# JLINK_OB_072.net
KiCad netlist of a schematic drawn in Altium Designer
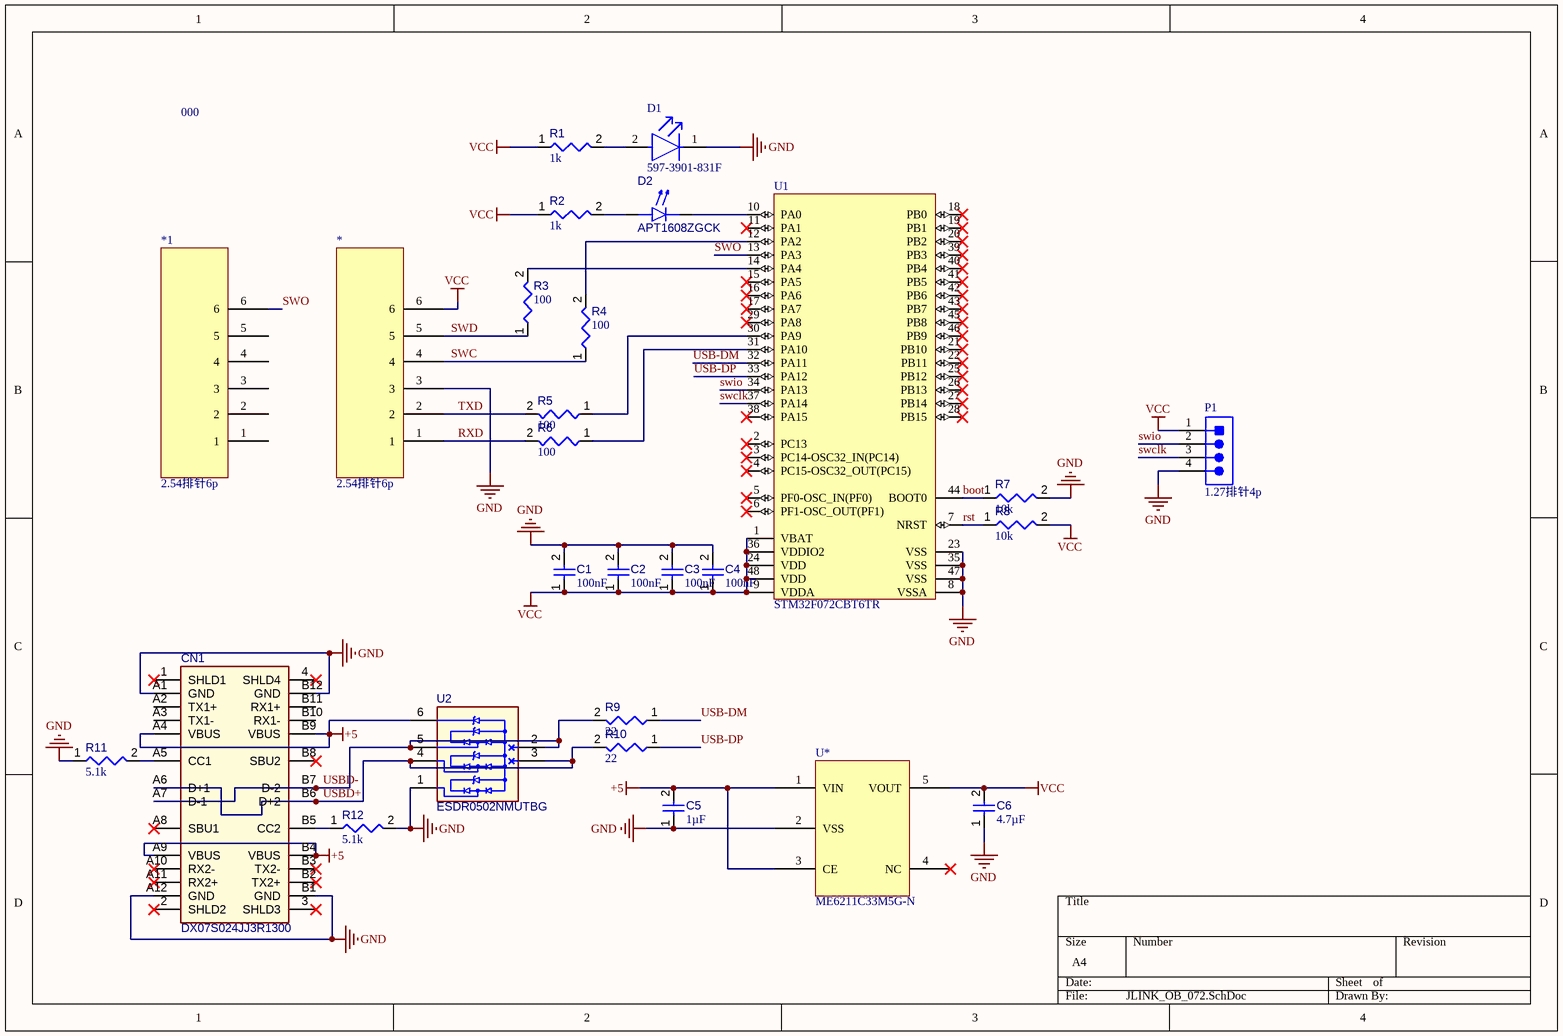
[diagram p0: JLINK_OB_072.SchDoc]

(export (version "E")
  (design (tool "Eeschema 10.0.6"))
  (components
    (comp (ref "*")
      (value "2.54排针6p")
      (footprint "HDR2.54-WS-6P")
      (libsource (lib "DigiPCBA Workspace") (part "2.54排针6p-Symbol-1"))
    )
    (comp (ref "*1")
      (value "2.54排针6p")
      (footprint "HDR2.54-WS-6P")
      (libsource (lib "DigiPCBA Workspace") (part "2.54排针6p-Symbol-1"))
    )
    (comp (ref "C1")
      (value "100nF")
      (footprint "CAPC1608X90X40NL10T20")
      (description "Chip Capacitor, 100 nF, +/- 10%, 50 V, 0603 (1608 Metric)")
      (fields (field (name "TOLERANCE") "10%") (field (name "Comment") "Capacitor 100 nF +/-10% 50 V 0603"))
      (libsource (lib "DigiPCBA Workspace") (part "CAP-NP-2"))
    )
    (comp (ref "C2")
      (value "100nF")
      (footprint "CAPC1608X90X40NL10T20")
      (description "Chip Capacitor, 100 nF, +/- 10%, 50 V, 0603 (1608 Metric)")
      (fields (field (name "TOLERANCE") "10%") (field (name "Comment") "Capacitor 100 nF +/-10% 50 V 0603"))
      (libsource (lib "DigiPCBA Workspace") (part "CAP-NP-2"))
    )
    (comp (ref "C3")
      (value "100nF")
      (footprint "CAPC1608X90X40NL10T20")
      (description "Chip Capacitor, 100 nF, +/- 10%, 50 V, 0603 (1608 Metric)")
      (fields (field (name "TOLERANCE") "10%") (field (name "Comment") "Capacitor 100 nF +/-10% 50 V 0603"))
      (libsource (lib "DigiPCBA Workspace") (part "CAP-NP-2"))
    )
    (comp (ref "C4")
      (value "100nF")
      (footprint "CAPC1608X90X40NL10T20")
      (description "Chip Capacitor, 100 nF, +/- 10%, 50 V, 0603 (1608 Metric)")
      (fields (field (name "TOLERANCE") "10%") (field (name "Comment") "Capacitor 100 nF +/-10% 50 V 0603"))
      (libsource (lib "DigiPCBA Workspace") (part "CAP-NP-2"))
    )
    (comp (ref "C5")
      (value "1µF")
      (footprint "CAPC1608X90X40LL10T20")
      (description "Chip Capacitor, 1 uF, +/- 10%, 25 V, 0603 (1608 Metric)")
      (fields (field (name "TOLERANCE") "10%") (field (name "Comment") "Capacitor 1 uF +/- 10% 25 V 0603"))
      (libsource (lib "DigiPCBA Workspace") (part "CAP-NP-2"))
    )
    (comp (ref "C6")
      (value "4.7µF")
      (footprint "CAPC0603(1608)100_L")
      (description "Chip Capacitor, 4.7µF +/-20%, 10V, 0603, Thickness 1 mm")
      (fields (field (name "TOLERANCE") "10%") (field (name "Comment") "Capacitor 4.7µF +/-20% 10V 0603"))
      (libsource (lib "DigiPCBA Workspace") (part "CAP-NP-2"))
    )
    (comp (ref "CN1")
      (value "DX07S024JJ3R1300")
      (footprint "JAE-DX07S024JJ3_V")
      (description "USB-C Connector, 20 V, 1.25 A, -30 to 80 degC, RoHS, Tape and Reel")
      (libsource (lib "DigiPCBA Workspace") (part "CMP-00171-5"))
    )
    (comp (ref "D1")
      (value "597-3901-831F")
      (footprint "FP-597-3901-831F-MFG")
      (description "Smd 0603 White 20Pc Smpl Strip / Dialight Corporation Rohs Compliant: Yes")
      (libsource (lib "DigiPCBA Workspace") (part "8706943c75ba83719d021d2fdc84c58"))
    )
    (comp (ref "D2")
      (value "APT1608ZGCK")
      (footprint "FP-APT1608ZGCK-MFG")
      (description "LED Uni-Color Green 515nm 2-Pin Chip LED T/R")
      (libsource (lib "DigiPCBA Workspace") (part "DIODE-LED-2"))
    )
    (comp (ref "P1")
      (value "1.27排针4p")
      (footprint "HDR1.27-LI-4P")
      (libsource (lib "DigiPCBA Workspace") (part "4p*1"))
    )
    (comp (ref "R1")
      (value "1k")
      (footprint "RESC1608X55X25ML10T15")
      (description "Chip Resistor, 1 KOhm, +/-1%, 0.1 W, -55 to 155 degC, 0603 (1608 Metric)")
      (fields (field (name "POWER") "100mW") (field (name "TOLERANCE") "1%"))
      (libsource (lib "DigiPCBA Workspace") (part "RES-2"))
    )
    (comp (ref "R2")
      (value "1k")
      (footprint "RESC1608X55X25ML10T15")
      (description "Chip Resistor, 1 KOhm, +/-1%, 0.1 W, -55 to 155 degC, 0603 (1608 Metric)")
      (fields (field (name "POWER") "100mW") (field (name "TOLERANCE") "1%"))
      (libsource (lib "DigiPCBA Workspace") (part "RES-2"))
    )
    (comp (ref "R3")
      (value "100")
      (footprint "FP-RC0603-0_55-MFG")
      (description "Res Thick Film 0603 100 Ohm 5% 1/10W ±100ppm/°C Molded SMD SMD Paper T/R")
      (fields (field (name "TOLERANCE") "5%") (field (name "Comment") "RC0603JR-07100RL"))
      (libsource (lib "DigiPCBA Workspace") (part "RES-2"))
    )
    (comp (ref "R4")
      (value "100")
      (footprint "FP-RC0603-0_55-MFG")
      (description "Res Thick Film 0603 100 Ohm 5% 1/10W ±100ppm/°C Molded SMD SMD Paper T/R")
      (fields (field (name "TOLERANCE") "5%") (field (name "Comment") "RC0603JR-07100RL"))
      (libsource (lib "DigiPCBA Workspace") (part "RES-2"))
    )
    (comp (ref "R5")
      (value "100")
      (footprint "FP-RC0603-0_55-MFG")
      (description "Res Thick Film 0603 100 Ohm 5% 1/10W ±100ppm/°C Molded SMD SMD Paper T/R")
      (fields (field (name "TOLERANCE") "5%") (field (name "Comment") "RC0603JR-07100RL"))
      (libsource (lib "DigiPCBA Workspace") (part "RES-2"))
    )
    (comp (ref "R6")
      (value "100")
      (footprint "FP-RC0603-0_55-MFG")
      (description "Res Thick Film 0603 100 Ohm 5% 1/10W ±100ppm/°C Molded SMD SMD Paper T/R")
      (fields (field (name "TOLERANCE") "5%") (field (name "Comment") "RC0603JR-07100RL"))
      (libsource (lib "DigiPCBA Workspace") (part "RES-2"))
    )
    (comp (ref "R7")
      (value "10k")
      (footprint "RESC1608X55X25ML10T15")
      (description "Chip Resistor, 10 KOhm, +/- 1%, 01 W, -55 to 155 degC, 0603 (1608 Metric)")
      (fields (field (name "POWER") "100mW") (field (name "TOLERANCE") "1%"))
      (libsource (lib "DigiPCBA Workspace") (part "RES-2"))
    )
    (comp (ref "R8")
      (value "10k")
      (footprint "RESC1608X55X25ML10T15")
      (description "Chip Resistor, 10 KOhm, +/- 1%, 01 W, -55 to 155 degC, 0603 (1608 Metric)")
      (fields (field (name "POWER") "100mW") (field (name "TOLERANCE") "1%"))
      (libsource (lib "DigiPCBA Workspace") (part "RES-2"))
    )
    (comp (ref "R9")
      (value "22")
      (footprint "RESC1609X50X30ML08T20")
      (description "Chip Resistor, 22 Ohm, +/- 1%, 100 mW, -55 to 155 degC, 0603 (1608 Metric)")
      (fields (field (name "POWER") "100mW") (field (name "TOLERANCE") "1%"))
      (libsource (lib "DigiPCBA Workspace") (part "RES-2"))
    )
    (comp (ref "R10")
      (value "22")
      (footprint "RESC1609X50X30ML08T20")
      (description "Chip Resistor, 22 Ohm, +/- 1%, 100 mW, -55 to 155 degC, 0603 (1608 Metric)")
      (fields (field (name "POWER") "100mW") (field (name "TOLERANCE") "1%"))
      (libsource (lib "DigiPCBA Workspace") (part "RES-2"))
    )
    (comp (ref "R11")
      (value "5.1k")
      (footprint "FP-RC1608-MFG")
      (description "Res Thick Film 0603 5.1K Ohm 5% 1/10W ±100ppm/°C Molded SMD SMD T/R")
      (fields (field (name "TOLERANCE") "5%") (field (name "Comment") "RC1608J512CS"))
      (libsource (lib "DigiPCBA Workspace") (part "RES-2"))
    )
    (comp (ref "R12")
      (value "5.1k")
      (footprint "FP-RC1608-MFG")
      (description "Res Thick Film 0603 5.1K Ohm 5% 1/10W ±100ppm/°C Molded SMD SMD T/R")
      (fields (field (name "TOLERANCE") "5%") (field (name "Comment") "RC1608J512CS"))
      (libsource (lib "DigiPCBA Workspace") (part "RES-2"))
    )
    (comp (ref "U*")
      (value "ME6211C33M5G-N")
      (footprint "SOT23-5N")
      (description "VIN=6.5V Vo=3.3V Io=600mA")
      (libsource (lib "DigiPCBA Workspace") (part "ME6211C33M5G-N-Symbol-1"))
    )
    (comp (ref "U1")
      (value "STM32F072CBT6TR")
      (footprint "LQFP48 7X7_N")
      (description "MCU 32-Bit GP STM32F 32MHz ARM Cortex M0+ RISC 128kB Flash 48-Pin LQFP T/R")
      (libsource (lib "DigiPCBA Workspace") (part "MC-ARM-STM32F07X-LQFP48"))
    )
    (comp (ref "U2")
      (value "ESDR0502NMUTBG")
      (footprint "ONSC-UDFN-6-517AA-01_V")
      (libsource (lib "DigiPCBA Workspace") (part "CMP-00124-4"))
    )
  )
  (nets
    (net (code "1") (name "+5") (class "Default")
      (node (ref "C5") (pin "2") (pinfunction "2_2") (pintype "passive"))
      (node (ref "CN1") (pin "A4") (pinfunction "VBUS_A4") (pintype "passive"))
      (node (ref "CN1") (pin "A9") (pinfunction "VBUS_A9") (pintype "passive"))
      (node (ref "CN1") (pin "B4") (pinfunction "VBUS_B4") (pintype "passive"))
      (node (ref "CN1") (pin "B9") (pinfunction "VBUS_B9") (pintype "passive"))
      (node (ref "U*") (pin "1") (pinfunction "VIN_1") (pintype "passive"))
      (node (ref "U*") (pin "3") (pinfunction "CE_3") (pintype "passive"))
      (node (ref "U2") (pin "6") (pinfunction "VBUS_6") (pintype "power_in"))
    )
    (net (code "2") (name "/RXD") (class "Default")
      (node (ref "*") (pin "1") (pinfunction "1_1") (pintype "passive"))
      (node (ref "R6") (pin "2") (pinfunction "2_2") (pintype "passive"))
    )
    (net (code "3") (name "/SWC") (class "Default")
      (node (ref "*") (pin "4") (pinfunction "4_4") (pintype "passive"))
      (node (ref "R4") (pin "1") (pinfunction "1_1") (pintype "passive"))
    )
    (net (code "4") (name "/SWD") (class "Default")
      (node (ref "*") (pin "5") (pinfunction "5_5") (pintype "passive"))
      (node (ref "R3") (pin "1") (pinfunction "1_1") (pintype "passive"))
    )
    (net (code "5") (name "/SWO") (class "Default")
      (node (ref "*1") (pin "6") (pinfunction "6_6") (pintype "passive"))
      (node (ref "U1") (pin "13") (pinfunction "PA3_13") (pintype "bidirectional"))
    )
    (net (code "6") (name "/TXD") (class "Default")
      (node (ref "*") (pin "2") (pinfunction "2_2") (pintype "passive"))
      (node (ref "R5") (pin "2") (pinfunction "2_2") (pintype "passive"))
    )
    (net (code "7") (name "/USB-DM") (class "Default")
      (node (ref "R9") (pin "1") (pinfunction "1_1") (pintype "passive"))
      (node (ref "U1") (pin "32") (pinfunction "PA11_32") (pintype "bidirectional"))
    )
    (net (code "8") (name "/USB-DP") (class "Default")
      (node (ref "R10") (pin "1") (pinfunction "1_1") (pintype "passive"))
      (node (ref "U1") (pin "33") (pinfunction "PA12_33") (pintype "bidirectional"))
    )
    (net (code "9") (name "/USBD+") (class "Default")
      (node (ref "CN1") (pin "A6") (pinfunction "D+1_A6") (pintype "passive"))
      (node (ref "CN1") (pin "B6") (pinfunction "D+2_B6") (pintype "passive"))
      (node (ref "R10") (pin "2") (pinfunction "2_2") (pintype "passive"))
      (node (ref "U2") (pin "3") (pinfunction "NC_3") (pintype "passive"))
      (node (ref "U2") (pin "4") (pinfunction "D-_4") (pintype "passive"))
    )
    (net (code "10") (name "/USBD-") (class "Default")
      (node (ref "CN1") (pin "A7") (pinfunction "D-1_A7") (pintype "passive"))
      (node (ref "CN1") (pin "B7") (pinfunction "D-2_B7") (pintype "passive"))
      (node (ref "R9") (pin "2") (pinfunction "2_2") (pintype "passive"))
      (node (ref "U2") (pin "2") (pinfunction "NC_2") (pintype "passive"))
      (node (ref "U2") (pin "5") (pinfunction "D+_5") (pintype "passive"))
    )
    (net (code "11") (name "/boot") (class "Default")
      (node (ref "R7") (pin "1") (pinfunction "1_1") (pintype "passive"))
      (node (ref "U1") (pin "44") (pinfunction "BOOT0_44") (pintype "passive"))
    )
    (net (code "12") (name "/rst") (class "Default")
      (node (ref "R8") (pin "1") (pinfunction "1_1") (pintype "passive"))
      (node (ref "U1") (pin "7") (pinfunction "NRST_7") (pintype "bidirectional"))
    )
    (net (code "13") (name "/swclk") (class "Default")
      (node (ref "P1") (pin "3") (pinfunction "3_3") (pintype "passive"))
      (node (ref "U1") (pin "37") (pinfunction "PA14_37") (pintype "bidirectional"))
    )
    (net (code "14") (name "/swio") (class "Default")
      (node (ref "P1") (pin "2") (pinfunction "2_2") (pintype "passive"))
      (node (ref "U1") (pin "34") (pinfunction "PA13_34") (pintype "bidirectional"))
    )
    (net (code "15") (name "GND") (class "Default")
      (node (ref "*") (pin "3") (pinfunction "3_3") (pintype "passive"))
      (node (ref "C1") (pin "2") (pinfunction "2_2") (pintype "passive"))
      (node (ref "C2") (pin "2") (pinfunction "2_2") (pintype "passive"))
      (node (ref "C3") (pin "2") (pinfunction "2_2") (pintype "passive"))
      (node (ref "C4") (pin "2") (pinfunction "2_2") (pintype "passive"))
      (node (ref "C5") (pin "1") (pinfunction "1_1") (pintype "passive"))
      (node (ref "C6") (pin "1") (pinfunction "1_1") (pintype "passive"))
      (node (ref "CN1") (pin "A1") (pinfunction "GND_A1") (pintype "passive"))
      (node (ref "CN1") (pin "A12") (pinfunction "GND_A12") (pintype "passive"))
      (node (ref "CN1") (pin "B1") (pinfunction "GND_B1") (pintype "passive"))
      (node (ref "CN1") (pin "B12") (pinfunction "GND_B12") (pintype "passive"))
      (node (ref "D1") (pin "1") (pinfunction "C_1") (pintype "passive"))
      (node (ref "P1") (pin "4") (pinfunction "4_4") (pintype "passive"))
      (node (ref "R11") (pin "1") (pinfunction "1_1") (pintype "passive"))
      (node (ref "R12") (pin "2") (pinfunction "2_2") (pintype "passive"))
      (node (ref "R7") (pin "2") (pinfunction "2_2") (pintype "passive"))
      (node (ref "U*") (pin "2") (pinfunction "VSS_2") (pintype "passive"))
      (node (ref "U1") (pin "23") (pinfunction "VSS_23") (pintype "power_in"))
      (node (ref "U1") (pin "35") (pinfunction "VSS_35") (pintype "power_in"))
      (node (ref "U1") (pin "47") (pinfunction "VSS_47") (pintype "power_in"))
      (node (ref "U1") (pin "8") (pinfunction "VSSA_8") (pintype "power_in"))
      (node (ref "U2") (pin "1") (pinfunction "GND_1") (pintype "power_in"))
    )
    (net (code "16") (name "Net-(CN1-CC1)") (class "Default")
      (node (ref "CN1") (pin "A5") (pinfunction "CC1_A5") (pintype "passive"))
      (node (ref "R11") (pin "2") (pinfunction "2_2") (pintype "passive"))
    )
    (net (code "17") (name "Net-(CN1-CC2)") (class "Default")
      (node (ref "CN1") (pin "B5") (pinfunction "CC2_B5") (pintype "passive"))
      (node (ref "R12") (pin "1") (pinfunction "1_1") (pintype "passive"))
    )
    (net (code "18") (name "Net-(D1-A)") (class "Default")
      (node (ref "D1") (pin "2") (pinfunction "A_2") (pintype "passive"))
      (node (ref "R1") (pin "2") (pinfunction "2_2") (pintype "passive"))
    )
    (net (code "19") (name "Net-(D2-A)") (class "Default")
      (node (ref "D2") (pin "2") (pinfunction "A_2") (pintype "passive"))
      (node (ref "R2") (pin "2") (pinfunction "2_2") (pintype "passive"))
    )
    (net (code "20") (name "Net-(D2-K)") (class "Default")
      (node (ref "D2") (pin "1") (pinfunction "K_1") (pintype "passive"))
      (node (ref "U1") (pin "10") (pinfunction "PA0_10") (pintype "bidirectional"))
    )
    (net (code "21") (name "Net-(U1-PA2)") (class "Default")
      (node (ref "R4") (pin "2") (pinfunction "2_2") (pintype "passive"))
      (node (ref "U1") (pin "12") (pinfunction "PA2_12") (pintype "bidirectional"))
    )
    (net (code "22") (name "Net-(U1-PA4)") (class "Default")
      (node (ref "R3") (pin "2") (pinfunction "2_2") (pintype "passive"))
      (node (ref "U1") (pin "14") (pinfunction "PA4_14") (pintype "bidirectional"))
    )
    (net (code "23") (name "Net-(U1-PA9)") (class "Default")
      (node (ref "R5") (pin "1") (pinfunction "1_1") (pintype "passive"))
      (node (ref "U1") (pin "30") (pinfunction "PA9_30") (pintype "bidirectional"))
    )
    (net (code "24") (name "Net-(U1-PA10)") (class "Default")
      (node (ref "R6") (pin "1") (pinfunction "1_1") (pintype "passive"))
      (node (ref "U1") (pin "31") (pinfunction "PA10_31") (pintype "bidirectional"))
    )
    (net (code "25") (name "VCC") (class "Default")
      (node (ref "*") (pin "6") (pinfunction "6_6") (pintype "passive"))
      (node (ref "C1") (pin "1") (pinfunction "1_1") (pintype "passive"))
      (node (ref "C2") (pin "1") (pinfunction "1_1") (pintype "passive"))
      (node (ref "C3") (pin "1") (pinfunction "1_1") (pintype "passive"))
      (node (ref "C4") (pin "1") (pinfunction "1_1") (pintype "passive"))
      (node (ref "C6") (pin "2") (pinfunction "2_2") (pintype "passive"))
      (node (ref "P1") (pin "1") (pinfunction "1_1") (pintype "passive"))
      (node (ref "R1") (pin "1") (pinfunction "1_1") (pintype "passive"))
      (node (ref "R2") (pin "1") (pinfunction "1_1") (pintype "passive"))
      (node (ref "R8") (pin "2") (pinfunction "2_2") (pintype "passive"))
      (node (ref "U*") (pin "5") (pinfunction "VOUT_5") (pintype "passive"))
      (node (ref "U1") (pin "1") (pinfunction "VBAT_1") (pintype "power_in"))
      (node (ref "U1") (pin "24") (pinfunction "VDD_24") (pintype "power_in"))
      (node (ref "U1") (pin "36") (pinfunction "VDDIO2_36") (pintype "power_in"))
      (node (ref "U1") (pin "48") (pinfunction "VDD_48") (pintype "power_in"))
      (node (ref "U1") (pin "9") (pinfunction "VDDA_9") (pintype "power_in"))
    )
    (net (code "26") (name "unconnected-(*1-Pad1)") (class "Default")
      (node (ref "*1") (pin "1") (pinfunction "1_1") (pintype "passive"))
    )
    (net (code "27") (name "unconnected-(*1-Pad2)") (class "Default")
      (node (ref "*1") (pin "2") (pinfunction "2_2") (pintype "passive"))
    )
    (net (code "28") (name "unconnected-(*1-Pad3)") (class "Default")
      (node (ref "*1") (pin "3") (pinfunction "3_3") (pintype "passive"))
    )
    (net (code "29") (name "unconnected-(*1-Pad4)") (class "Default")
      (node (ref "*1") (pin "4") (pinfunction "4_4") (pintype "passive"))
    )
    (net (code "30") (name "unconnected-(*1-Pad5)") (class "Default")
      (node (ref "*1") (pin "5") (pinfunction "5_5") (pintype "passive"))
    )
    (net (code "31") (name "unconnected-(CN1-RX1+-PadB11)") (class "Default")
      (node (ref "CN1") (pin "B11") (pinfunction "RX1+_B11") (pintype "passive"))
    )
    (net (code "32") (name "unconnected-(CN1-RX1--PadB10)") (class "Default")
      (node (ref "CN1") (pin "B10") (pinfunction "RX1-_B10") (pintype "passive"))
    )
    (net (code "33") (name "unconnected-(CN1-RX2+-PadA11)") (class "Default")
      (node (ref "CN1") (pin "A11") (pinfunction "RX2+_A11") (pintype "passive+no_connect"))
    )
    (net (code "34") (name "unconnected-(CN1-RX2--PadA10)") (class "Default")
      (node (ref "CN1") (pin "A10") (pinfunction "RX2-_A10") (pintype "passive+no_connect"))
    )
    (net (code "35") (name "unconnected-(CN1-SBU1-PadA8)") (class "Default")
      (node (ref "CN1") (pin "A8") (pinfunction "SBU1_A8") (pintype "passive+no_connect"))
    )
    (net (code "36") (name "unconnected-(CN1-SBU2-PadB8)") (class "Default")
      (node (ref "CN1") (pin "B8") (pinfunction "SBU2_B8") (pintype "passive+no_connect"))
    )
    (net (code "37") (name "unconnected-(CN1-SHLD1-Pad1)") (class "Default")
      (node (ref "CN1") (pin "1") (pinfunction "SHLD1_1") (pintype "passive+no_connect"))
    )
    (net (code "38") (name "unconnected-(CN1-SHLD2-Pad2)") (class "Default")
      (node (ref "CN1") (pin "2") (pinfunction "SHLD2_2") (pintype "passive+no_connect"))
    )
    (net (code "39") (name "unconnected-(CN1-SHLD3-Pad3)") (class "Default")
      (node (ref "CN1") (pin "3") (pinfunction "SHLD3_3") (pintype "passive+no_connect"))
    )
    (net (code "40") (name "unconnected-(CN1-SHLD4-Pad4)") (class "Default")
      (node (ref "CN1") (pin "4") (pinfunction "SHLD4_4") (pintype "passive+no_connect"))
    )
    (net (code "41") (name "unconnected-(CN1-TX1+-PadA2)") (class "Default")
      (node (ref "CN1") (pin "A2") (pinfunction "TX1+_A2") (pintype "passive"))
    )
    (net (code "42") (name "unconnected-(CN1-TX1--PadA3)") (class "Default")
      (node (ref "CN1") (pin "A3") (pinfunction "TX1-_A3") (pintype "passive"))
    )
    (net (code "43") (name "unconnected-(CN1-TX2+-PadB2)") (class "Default")
      (node (ref "CN1") (pin "B2") (pinfunction "TX2+_B2") (pintype "passive+no_connect"))
    )
    (net (code "44") (name "unconnected-(CN1-TX2--PadB3)") (class "Default")
      (node (ref "CN1") (pin "B3") (pinfunction "TX2-_B3") (pintype "passive+no_connect"))
    )
    (net (code "45") (name "unconnected-(U*-NC-Pad4)") (class "Default")
      (node (ref "U*") (pin "4") (pinfunction "NC_4") (pintype "passive+no_connect"))
    )
    (net (code "46") (name "unconnected-(U1-PA1-Pad11)") (class "Default")
      (node (ref "U1") (pin "11") (pinfunction "PA1_11") (pintype "bidirectional+no_connect"))
    )
    (net (code "47") (name "unconnected-(U1-PA5-Pad15)") (class "Default")
      (node (ref "U1") (pin "15") (pinfunction "PA5_15") (pintype "bidirectional+no_connect"))
    )
    (net (code "48") (name "unconnected-(U1-PA6-Pad16)") (class "Default")
      (node (ref "U1") (pin "16") (pinfunction "PA6_16") (pintype "bidirectional+no_connect"))
    )
    (net (code "49") (name "unconnected-(U1-PA7-Pad17)") (class "Default")
      (node (ref "U1") (pin "17") (pinfunction "PA7_17") (pintype "bidirectional+no_connect"))
    )
    (net (code "50") (name "unconnected-(U1-PA8-Pad29)") (class "Default")
      (node (ref "U1") (pin "29") (pinfunction "PA8_29") (pintype "bidirectional+no_connect"))
    )
    (net (code "51") (name "unconnected-(U1-PA15-Pad38)") (class "Default")
      (node (ref "U1") (pin "38") (pinfunction "PA15_38") (pintype "bidirectional+no_connect"))
    )
    (net (code "52") (name "unconnected-(U1-PB0-Pad18)") (class "Default")
      (node (ref "U1") (pin "18") (pinfunction "PB0_18") (pintype "bidirectional+no_connect"))
    )
    (net (code "53") (name "unconnected-(U1-PB1-Pad19)") (class "Default")
      (node (ref "U1") (pin "19") (pinfunction "PB1_19") (pintype "bidirectional+no_connect"))
    )
    (net (code "54") (name "unconnected-(U1-PB2-Pad20)") (class "Default")
      (node (ref "U1") (pin "20") (pinfunction "PB2_20") (pintype "bidirectional+no_connect"))
    )
    (net (code "55") (name "unconnected-(U1-PB3-Pad39)") (class "Default")
      (node (ref "U1") (pin "39") (pinfunction "PB3_39") (pintype "bidirectional+no_connect"))
    )
    (net (code "56") (name "unconnected-(U1-PB4-Pad40)") (class "Default")
      (node (ref "U1") (pin "40") (pinfunction "PB4_40") (pintype "bidirectional+no_connect"))
    )
    (net (code "57") (name "unconnected-(U1-PB5-Pad41)") (class "Default")
      (node (ref "U1") (pin "41") (pinfunction "PB5_41") (pintype "bidirectional+no_connect"))
    )
    (net (code "58") (name "unconnected-(U1-PB6-Pad42)") (class "Default")
      (node (ref "U1") (pin "42") (pinfunction "PB6_42") (pintype "bidirectional+no_connect"))
    )
    (net (code "59") (name "unconnected-(U1-PB7-Pad43)") (class "Default")
      (node (ref "U1") (pin "43") (pinfunction "PB7_43") (pintype "bidirectional+no_connect"))
    )
    (net (code "60") (name "unconnected-(U1-PB8-Pad45)") (class "Default")
      (node (ref "U1") (pin "45") (pinfunction "PB8_45") (pintype "bidirectional+no_connect"))
    )
    (net (code "61") (name "unconnected-(U1-PB9-Pad46)") (class "Default")
      (node (ref "U1") (pin "46") (pinfunction "PB9_46") (pintype "bidirectional+no_connect"))
    )
    (net (code "62") (name "unconnected-(U1-PB10-Pad21)") (class "Default")
      (node (ref "U1") (pin "21") (pinfunction "PB10_21") (pintype "bidirectional+no_connect"))
    )
    (net (code "63") (name "unconnected-(U1-PB11-Pad22)") (class "Default")
      (node (ref "U1") (pin "22") (pinfunction "PB11_22") (pintype "bidirectional+no_connect"))
    )
    (net (code "64") (name "unconnected-(U1-PB12-Pad25)") (class "Default")
      (node (ref "U1") (pin "25") (pinfunction "PB12_25") (pintype "bidirectional+no_connect"))
    )
    (net (code "65") (name "unconnected-(U1-PB13-Pad26)") (class "Default")
      (node (ref "U1") (pin "26") (pinfunction "PB13_26") (pintype "bidirectional+no_connect"))
    )
    (net (code "66") (name "unconnected-(U1-PB14-Pad27)") (class "Default")
      (node (ref "U1") (pin "27") (pinfunction "PB14_27") (pintype "bidirectional+no_connect"))
    )
    (net (code "67") (name "unconnected-(U1-PB15-Pad28)") (class "Default")
      (node (ref "U1") (pin "28") (pinfunction "PB15_28") (pintype "bidirectional+no_connect"))
    )
    (net (code "68") (name "unconnected-(U1-PC13-Pad2)") (class "Default")
      (node (ref "U1") (pin "2") (pinfunction "PC13_2") (pintype "bidirectional+no_connect"))
    )
    (net (code "69") (name "unconnected-(U1-PC14-OSC32_IN(PC14)-Pad3)") (class "Default")
      (node (ref "U1") (pin "3") (pinfunction "PC14-OSC32_IN(PC14)_3") (pintype "bidirectional+no_connect"))
    )
    (net (code "70") (name "unconnected-(U1-PC15-OSC32_OUT(PC15)-Pad4)") (class "Default")
      (node (ref "U1") (pin "4") (pinfunction "PC15-OSC32_OUT(PC15)_4") (pintype "bidirectional+no_connect"))
    )
    (net (code "71") (name "unconnected-(U1-PF0-OSC_IN(PF0)-Pad5)") (class "Default")
      (node (ref "U1") (pin "5") (pinfunction "PF0-OSC_IN(PF0)_5") (pintype "bidirectional+no_connect"))
    )
    (net (code "72") (name "unconnected-(U1-PF1-OSC_OUT(PF1)-Pad6)") (class "Default")
      (node (ref "U1") (pin "6") (pinfunction "PF1-OSC_OUT(PF1)_6") (pintype "bidirectional+no_connect"))
    )
  )
)
